# moscow_esp8266_reva.net
KiCad netlist of a schematic drawn in EAGLE
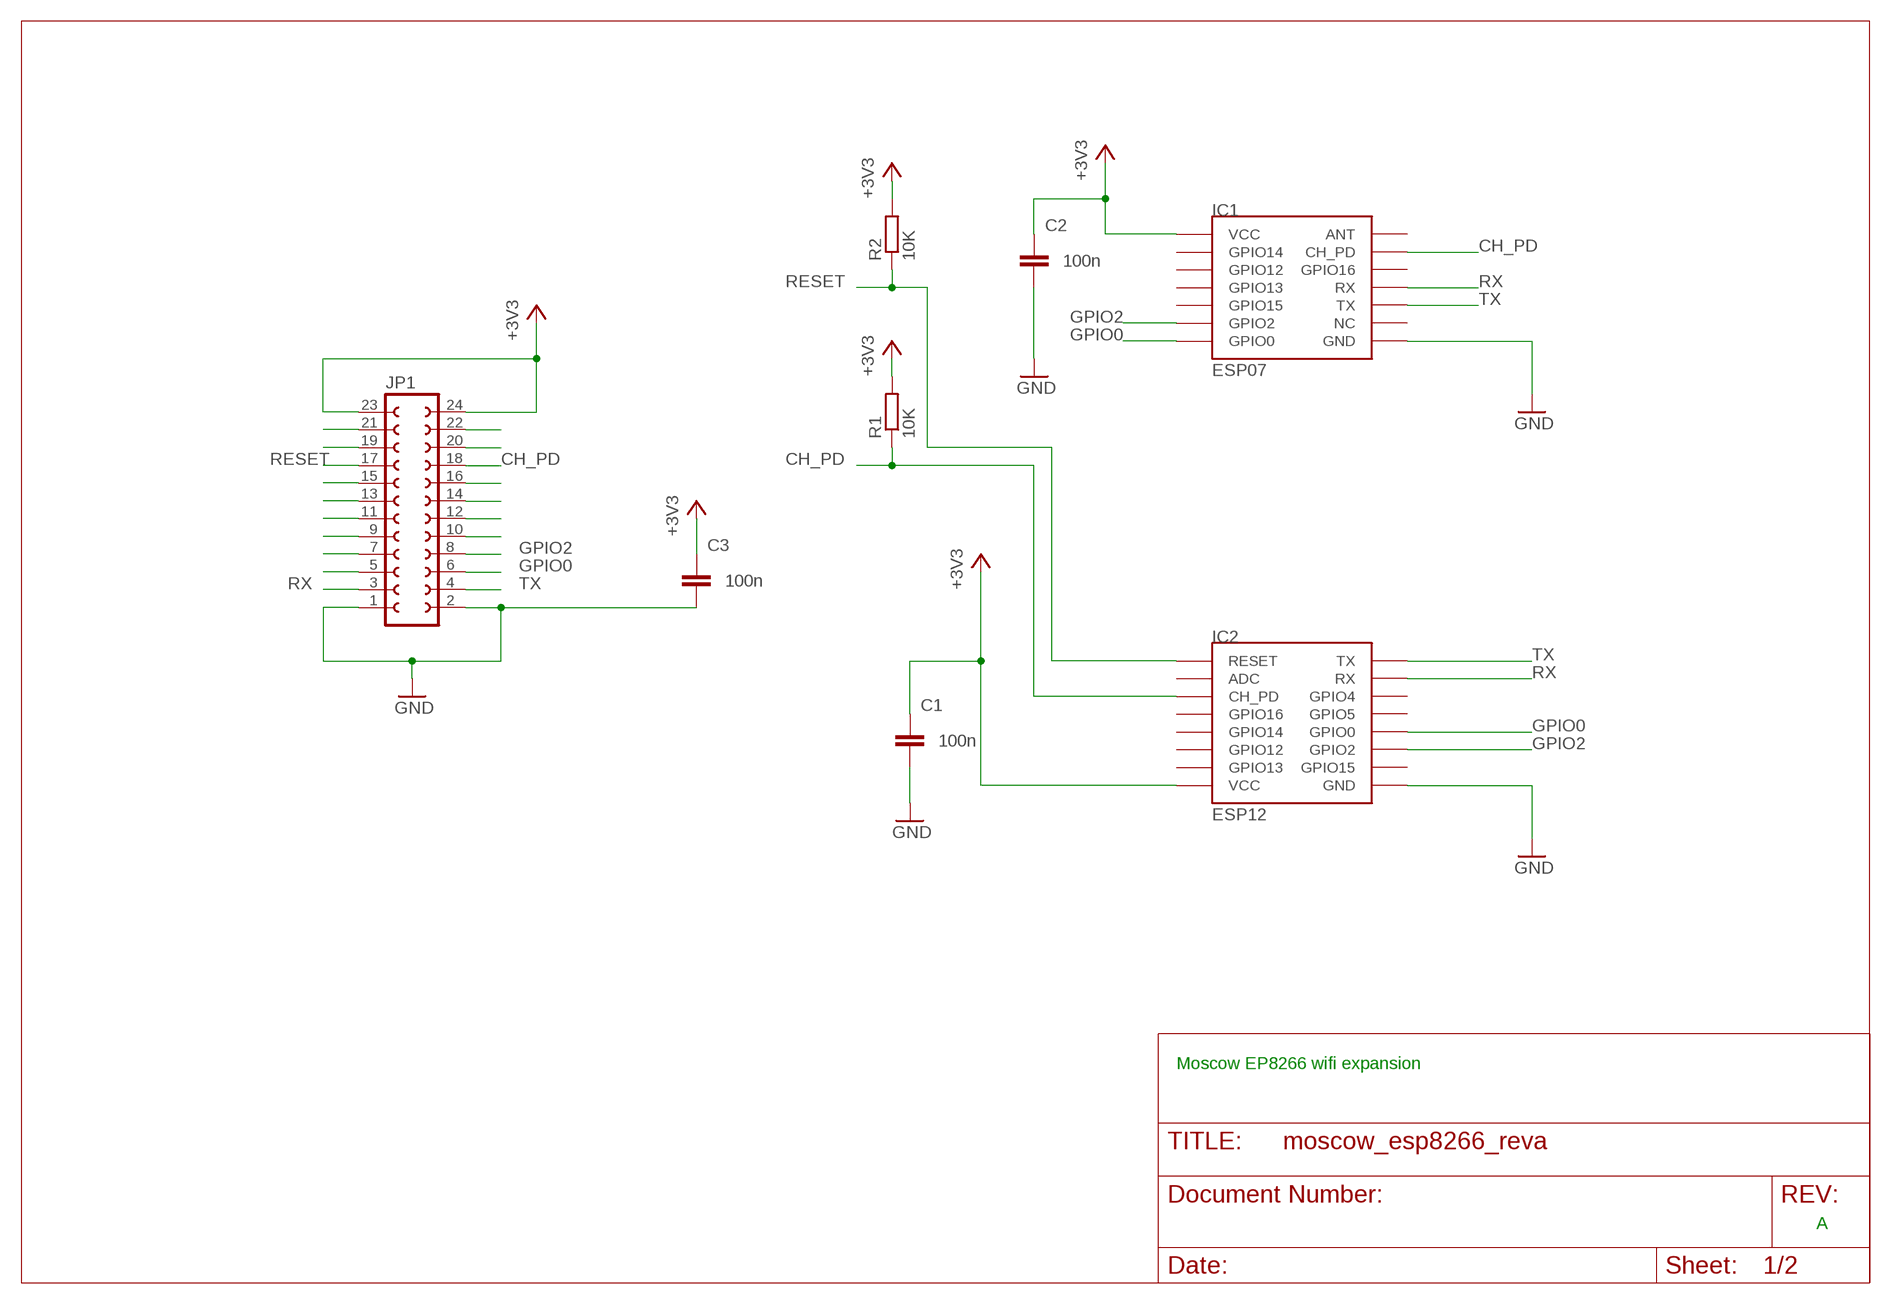
[diagram p0: schematic, sheet 1]
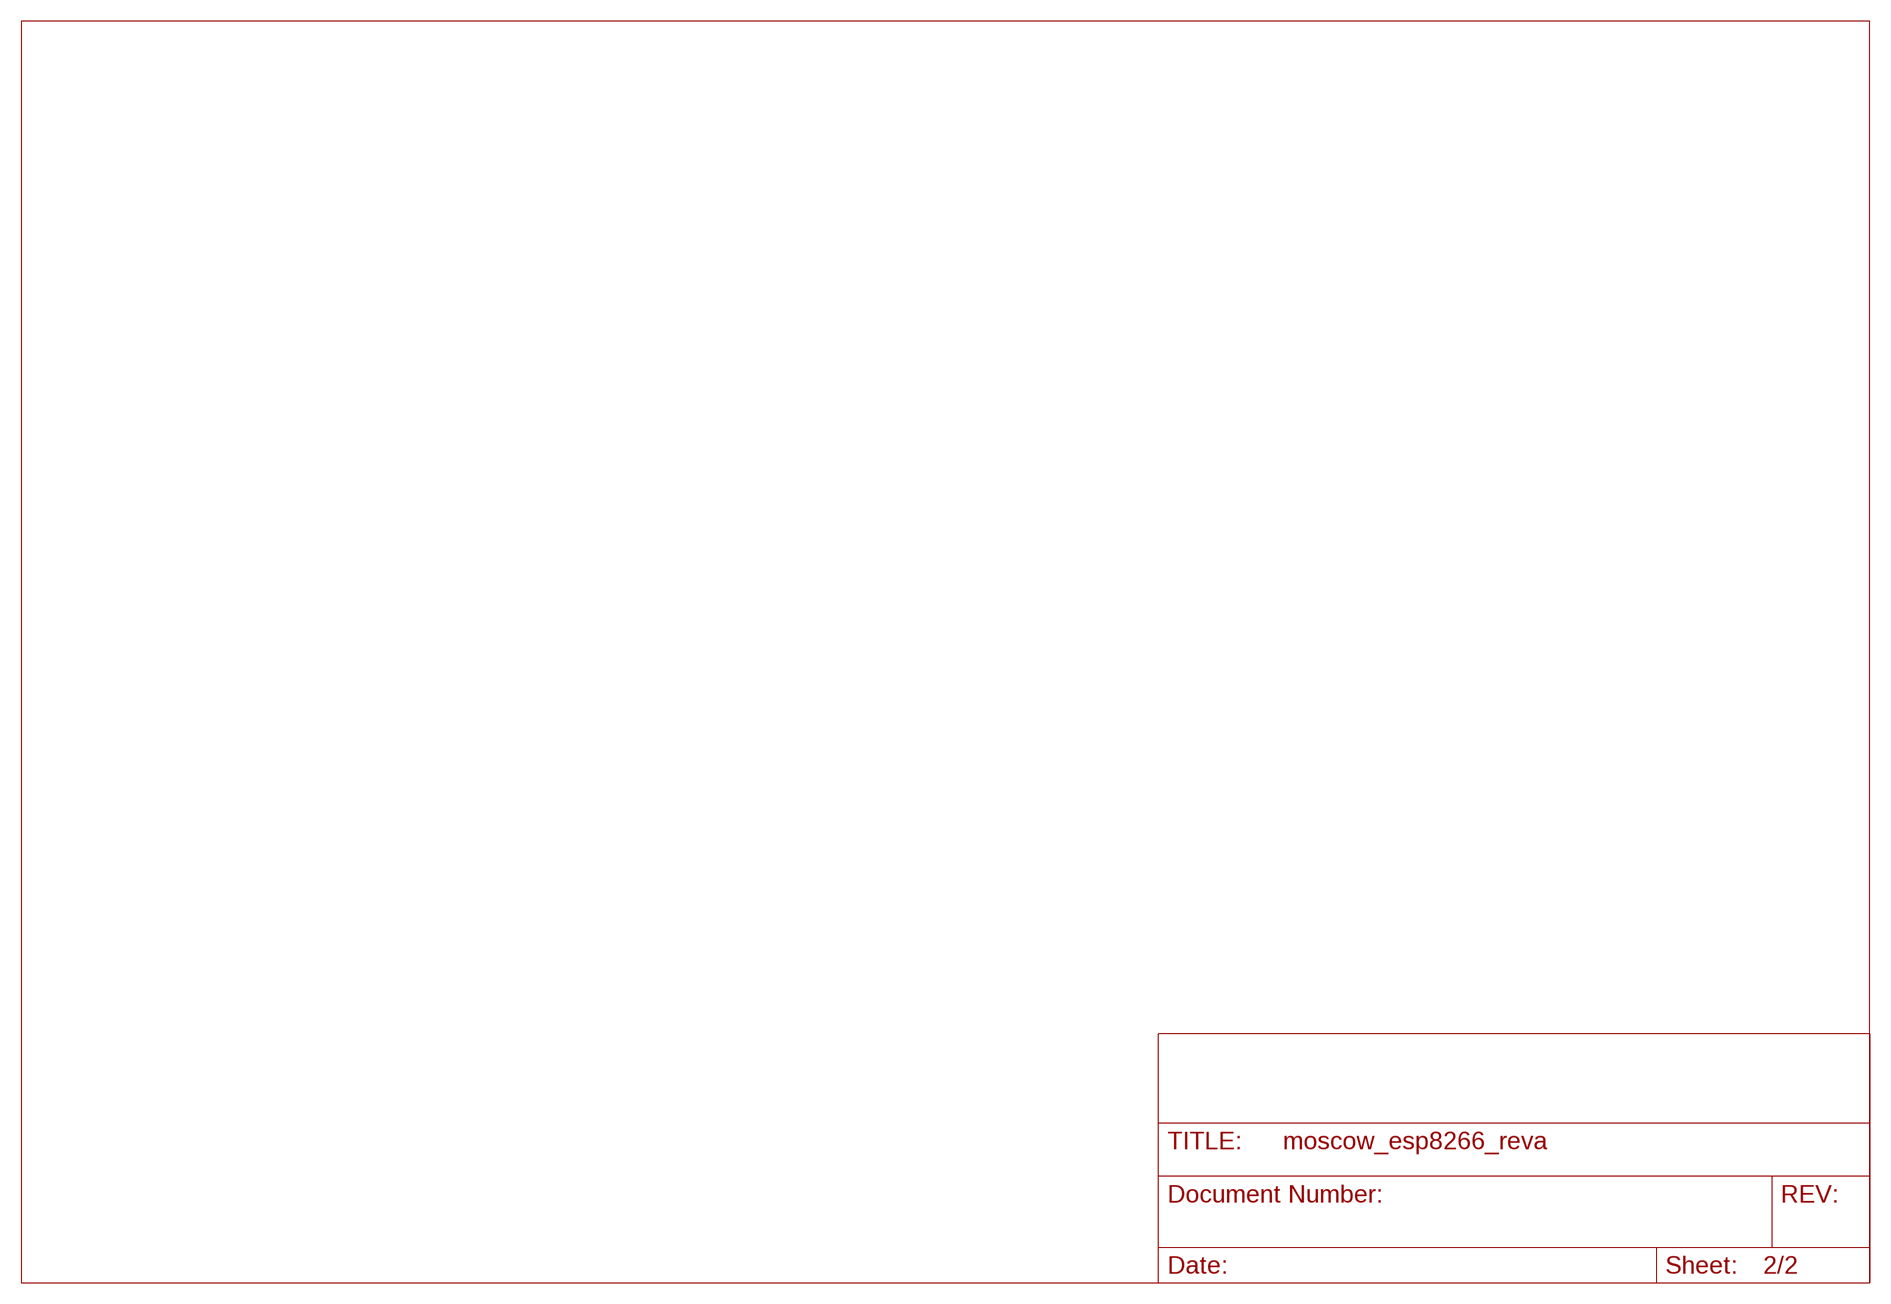
[diagram p1: schematic, sheet 2]

(export (version "E")
  (design (tool "Eeschema 10.0.6"))
  (components
    (comp (ref "C1")
      (value "100n")
      (footprint "eagle-import:C0805")
      (libsource (lib "eagle-import") (part "C-EUC0805"))
    )
    (comp (ref "C2")
      (value "100n")
      (footprint "eagle-import:C0805")
      (libsource (lib "eagle-import") (part "C-EUC0805"))
    )
    (comp (ref "C3")
      (value "100n")
      (footprint "eagle-import:C0805")
      (libsource (lib "eagle-import") (part "C-EUC0805"))
    )
    (comp (ref "IC1")
      (value "ESP07")
      (footprint "eagle-import:ESP07")
      (libsource (lib "eagle-import") (part "ESP07"))
    )
    (comp (ref "IC2")
      (value "ESP12")
      (footprint "eagle-import:ESP12")
      (libsource (lib "eagle-import") (part "ESP12"))
    )
    (comp (ref "JP1")
      (value "FE12-2")
      (footprint "eagle-import:FE12-2")
      (libsource (lib "eagle-import") (part "FE12-2"))
    )
    (comp (ref "R1")
      (value "10K")
      (footprint "eagle-import:R0805")
      (libsource (lib "eagle-import") (part "R-EU_R0805"))
    )
    (comp (ref "R2")
      (value "10K")
      (footprint "eagle-import:R0805")
      (libsource (lib "eagle-import") (part "R-EU_R0805"))
    )
  )
  (nets
    (net (code "1") (name "+3V3") (class "Default")
      (node (ref "C1") (pin "1") (pinfunction "1_1") (pintype "passive"))
      (node (ref "C2") (pin "1") (pinfunction "1_1") (pintype "passive"))
      (node (ref "C3") (pin "1") (pinfunction "1_1") (pintype "passive"))
      (node (ref "IC1") (pin "VCC") (pinfunction "VCC_VCC") (pintype "bidirectional"))
      (node (ref "IC2") (pin "VCC") (pinfunction "VCC_VCC") (pintype "bidirectional"))
      (node (ref "JP1") (pin "23") (pinfunction "23_23") (pintype "passive"))
      (node (ref "JP1") (pin "24") (pinfunction "24_24") (pintype "passive"))
      (node (ref "R1") (pin "2") (pinfunction "2_2") (pintype "passive"))
      (node (ref "R2") (pin "2") (pinfunction "2_2") (pintype "passive"))
    )
    (net (code "2") (name "CH_PD") (class "Default")
      (node (ref "IC1") (pin "CH_PD") (pinfunction "CH_PD_CH_PD") (pintype "bidirectional"))
      (node (ref "IC2") (pin "CH_PD") (pinfunction "CH_PD_CH_PD") (pintype "bidirectional"))
      (node (ref "JP1") (pin "18") (pinfunction "18_18") (pintype "passive"))
      (node (ref "R1") (pin "1") (pinfunction "1_1") (pintype "passive"))
    )
    (net (code "3") (name "GND") (class "Default")
      (node (ref "C1") (pin "2") (pinfunction "2_2") (pintype "passive"))
      (node (ref "C2") (pin "2") (pinfunction "2_2") (pintype "passive"))
      (node (ref "C3") (pin "2") (pinfunction "2_2") (pintype "passive"))
      (node (ref "IC1") (pin "GND") (pinfunction "GND_GND") (pintype "bidirectional"))
      (node (ref "IC2") (pin "GND") (pinfunction "GND_GND") (pintype "bidirectional"))
      (node (ref "JP1") (pin "1") (pinfunction "1_1") (pintype "passive"))
      (node (ref "JP1") (pin "2") (pinfunction "2_2") (pintype "passive"))
    )
    (net (code "4") (name "GPIO0") (class "Default")
      (node (ref "IC1") (pin "GPIO0") (pinfunction "GPIO0_GPIO0") (pintype "bidirectional"))
      (node (ref "IC2") (pin "GPIO0") (pinfunction "GPIO0_GPIO0") (pintype "bidirectional"))
      (node (ref "JP1") (pin "6") (pinfunction "6_6") (pintype "passive"))
    )
    (net (code "5") (name "GPIO2") (class "Default")
      (node (ref "IC1") (pin "GPIO2") (pinfunction "GPIO2_GPIO2") (pintype "bidirectional"))
      (node (ref "IC2") (pin "GPIO2") (pinfunction "GPIO2_GPIO2") (pintype "bidirectional"))
      (node (ref "JP1") (pin "8") (pinfunction "8_8") (pintype "passive"))
    )
    (net (code "6") (name "RESET") (class "Default")
      (node (ref "IC2") (pin "RESET") (pinfunction "RESET_RESET") (pintype "bidirectional"))
      (node (ref "JP1") (pin "17") (pinfunction "17_17") (pintype "passive"))
      (node (ref "R2") (pin "1") (pinfunction "1_1") (pintype "passive"))
    )
    (net (code "7") (name "RX") (class "Default")
      (node (ref "IC1") (pin "RX") (pinfunction "RX_RX") (pintype "bidirectional"))
      (node (ref "IC2") (pin "RX") (pinfunction "RX_RX") (pintype "bidirectional"))
      (node (ref "JP1") (pin "3") (pinfunction "3_3") (pintype "passive"))
    )
    (net (code "8") (name "TX") (class "Default")
      (node (ref "IC1") (pin "TX") (pinfunction "TX_TX") (pintype "bidirectional"))
      (node (ref "IC2") (pin "TX") (pinfunction "TX_TX") (pintype "bidirectional"))
      (node (ref "JP1") (pin "4") (pinfunction "4_4") (pintype "passive"))
    )
    (net (code "9") (name "unconnected-(IC1-PadANT)") (class "Default")
      (node (ref "IC1") (pin "ANT") (pinfunction "ANT_ANT") (pintype "bidirectional"))
    )
    (net (code "10") (name "unconnected-(IC1-PadGPIO12)") (class "Default")
      (node (ref "IC1") (pin "GPIO12") (pinfunction "GPIO12_GPIO12") (pintype "bidirectional"))
    )
    (net (code "11") (name "unconnected-(IC1-PadGPIO13)") (class "Default")
      (node (ref "IC1") (pin "GPIO13") (pinfunction "GPIO13_GPIO13") (pintype "bidirectional"))
    )
    (net (code "12") (name "unconnected-(IC1-PadGPIO14)") (class "Default")
      (node (ref "IC1") (pin "GPIO14") (pinfunction "GPIO14_GPIO14") (pintype "bidirectional"))
    )
    (net (code "13") (name "unconnected-(IC1-PadGPIO15)") (class "Default")
      (node (ref "IC1") (pin "GPIO15") (pinfunction "GPIO15_GPIO15") (pintype "bidirectional"))
    )
    (net (code "14") (name "unconnected-(IC1-PadGPIO16)") (class "Default")
      (node (ref "IC1") (pin "GPIO16") (pinfunction "GPIO16_GPIO16") (pintype "bidirectional"))
    )
    (net (code "15") (name "unconnected-(IC1-PadNC)") (class "Default")
      (node (ref "IC1") (pin "NC") (pinfunction "NC_NC") (pintype "bidirectional"))
    )
    (net (code "16") (name "unconnected-(IC2-PadADC)") (class "Default")
      (node (ref "IC2") (pin "ADC") (pinfunction "ADC_ADC") (pintype "bidirectional"))
    )
    (net (code "17") (name "unconnected-(IC2-PadGPIO4)") (class "Default")
      (node (ref "IC2") (pin "GPIO4") (pinfunction "GPIO4_GPIO4") (pintype "bidirectional"))
    )
    (net (code "18") (name "unconnected-(IC2-PadGPIO5)") (class "Default")
      (node (ref "IC2") (pin "GPIO5") (pinfunction "GPIO5_GPIO5") (pintype "bidirectional"))
    )
    (net (code "19") (name "unconnected-(IC2-PadGPIO12)") (class "Default")
      (node (ref "IC2") (pin "GPIO12") (pinfunction "GPIO12_GPIO12") (pintype "bidirectional"))
    )
    (net (code "20") (name "unconnected-(IC2-PadGPIO13)") (class "Default")
      (node (ref "IC2") (pin "GPIO13") (pinfunction "GPIO13_GPIO13") (pintype "bidirectional"))
    )
    (net (code "21") (name "unconnected-(IC2-PadGPIO14)") (class "Default")
      (node (ref "IC2") (pin "GPIO14") (pinfunction "GPIO14_GPIO14") (pintype "bidirectional"))
    )
    (net (code "22") (name "unconnected-(IC2-PadGPIO15)") (class "Default")
      (node (ref "IC2") (pin "GPIO15") (pinfunction "GPIO15_GPIO15") (pintype "bidirectional"))
    )
    (net (code "23") (name "unconnected-(IC2-PadGPIO16)") (class "Default")
      (node (ref "IC2") (pin "GPIO16") (pinfunction "GPIO16_GPIO16") (pintype "bidirectional"))
    )
    (net (code "24") (name "unconnected-(JP1-Pad5)") (class "Default")
      (node (ref "JP1") (pin "5") (pinfunction "5_5") (pintype "passive"))
    )
    (net (code "25") (name "unconnected-(JP1-Pad7)") (class "Default")
      (node (ref "JP1") (pin "7") (pinfunction "7_7") (pintype "passive"))
    )
    (net (code "26") (name "unconnected-(JP1-Pad9)") (class "Default")
      (node (ref "JP1") (pin "9") (pinfunction "9_9") (pintype "passive"))
    )
    (net (code "27") (name "unconnected-(JP1-Pad10)") (class "Default")
      (node (ref "JP1") (pin "10") (pinfunction "10_10") (pintype "passive"))
    )
    (net (code "28") (name "unconnected-(JP1-Pad11)") (class "Default")
      (node (ref "JP1") (pin "11") (pinfunction "11_11") (pintype "passive"))
    )
    (net (code "29") (name "unconnected-(JP1-Pad12)") (class "Default")
      (node (ref "JP1") (pin "12") (pinfunction "12_12") (pintype "passive"))
    )
    (net (code "30") (name "unconnected-(JP1-Pad13)") (class "Default")
      (node (ref "JP1") (pin "13") (pinfunction "13_13") (pintype "passive"))
    )
    (net (code "31") (name "unconnected-(JP1-Pad14)") (class "Default")
      (node (ref "JP1") (pin "14") (pinfunction "14_14") (pintype "passive"))
    )
    (net (code "32") (name "unconnected-(JP1-Pad15)") (class "Default")
      (node (ref "JP1") (pin "15") (pinfunction "15_15") (pintype "passive"))
    )
    (net (code "33") (name "unconnected-(JP1-Pad16)") (class "Default")
      (node (ref "JP1") (pin "16") (pinfunction "16_16") (pintype "passive"))
    )
    (net (code "34") (name "unconnected-(JP1-Pad19)") (class "Default")
      (node (ref "JP1") (pin "19") (pinfunction "19_19") (pintype "passive"))
    )
    (net (code "35") (name "unconnected-(JP1-Pad20)") (class "Default")
      (node (ref "JP1") (pin "20") (pinfunction "20_20") (pintype "passive"))
    )
    (net (code "36") (name "unconnected-(JP1-Pad21)") (class "Default")
      (node (ref "JP1") (pin "21") (pinfunction "21_21") (pintype "passive"))
    )
    (net (code "37") (name "unconnected-(JP1-Pad22)") (class "Default")
      (node (ref "JP1") (pin "22") (pinfunction "22_22") (pintype "passive"))
    )
  )
)
